# stm.net
KiCad netlist of a schematic drawn in Altium Designer
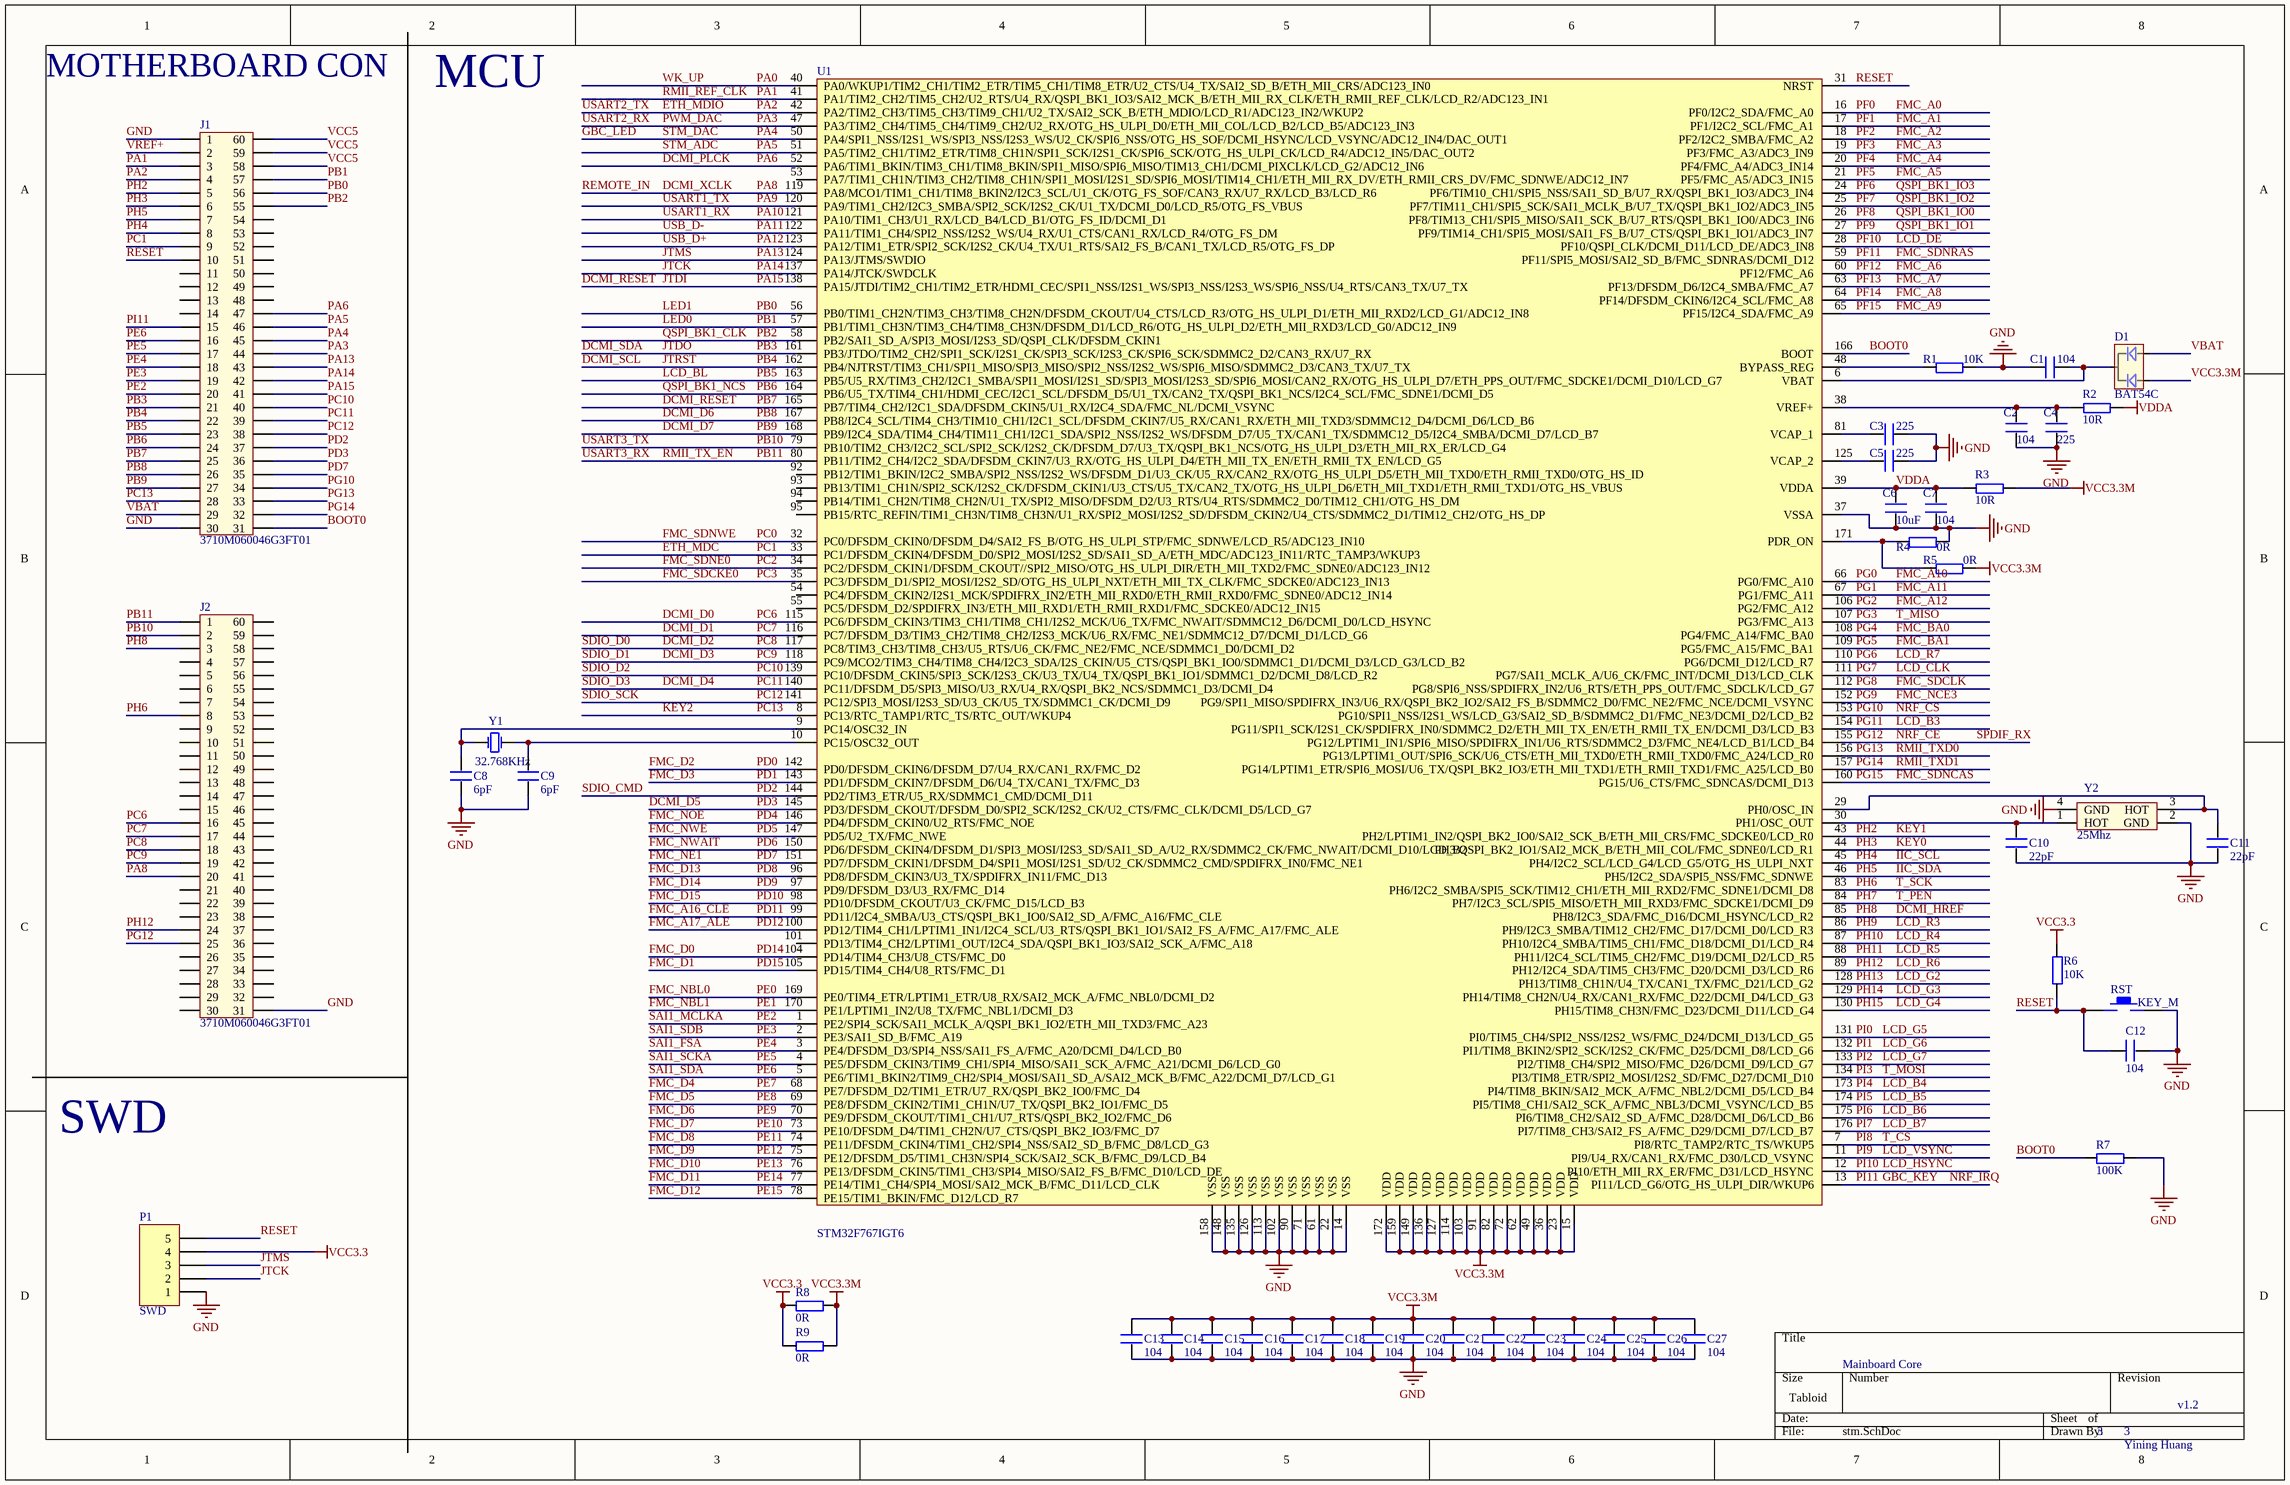
[diagram p0: stm.SchDoc]

(export (version "E")
  (design (tool "Eeschema 10.0.6"))
  (components
    (comp (ref "C1") (value "104") (footprint "0805") (libsource (lib "STM32F767核心板封装库") (part "C")))
    (comp (ref "C2") (value "104") (footprint "0805") (libsource (lib "STM32F767核心板封装库") (part "C")))
    (comp (ref "C3") (value "225") (footprint "0805") (libsource (lib "STM32F767核心板封装库") (part "C")))
    (comp (ref "C4") (value "225") (footprint "0805") (libsource (lib "STM32F767核心板封装库") (part "C")))
    (comp (ref "C5") (value "225") (footprint "0805") (libsource (lib "STM32F767核心板封装库") (part "C")))
    (comp (ref "C6") (value "10uF") (footprint "0805") (libsource (lib "STM32F767核心板封装库") (part "C")))
    (comp (ref "C7") (value "104") (footprint "0805") (libsource (lib "STM32F767核心板封装库") (part "C")))
    (comp (ref "C8") (value "6pF") (footprint "0805") (libsource (lib "STM32F767核心板封装库") (part "C")))
    (comp (ref "C9") (value "6pF") (footprint "0805") (libsource (lib "STM32F767核心板封装库") (part "C")))
    (comp (ref "C10") (value "22pF") (footprint "0805") (libsource (lib "STM32F767核心板封装库") (part "C")))
    (comp (ref "C11") (value "22pF") (footprint "0805") (libsource (lib "STM32F767核心板封装库") (part "C")))
    (comp (ref "C12") (value "104") (footprint "0805") (libsource (lib "STM32F767核心板封装库") (part "C")))
    (comp (ref "C13") (value "104") (footprint "0805") (libsource (lib "STM32F767核心板封装库") (part "C")))
    (comp (ref "C14") (value "104") (footprint "0805") (libsource (lib "STM32F767核心板封装库") (part "C")))
    (comp (ref "C15") (value "104") (footprint "0805") (libsource (lib "STM32F767核心板封装库") (part "C")))
    (comp (ref "C16") (value "104") (footprint "0805") (libsource (lib "STM32F767核心板封装库") (part "C")))
    (comp (ref "C17") (value "104") (footprint "0805") (libsource (lib "STM32F767核心板封装库") (part "C")))
    (comp (ref "C18") (value "104") (footprint "0805") (libsource (lib "STM32F767核心板封装库") (part "C")))
    (comp (ref "C19") (value "104") (footprint "0805") (libsource (lib "STM32F767核心板封装库") (part "C")))
    (comp (ref "C20") (value "104") (footprint "0805") (libsource (lib "STM32F767核心板封装库") (part "C")))
    (comp (ref "C21") (value "104") (footprint "0805") (libsource (lib "STM32F767核心板封装库") (part "C")))
    (comp (ref "C22") (value "104") (footprint "0805") (libsource (lib "STM32F767核心板封装库") (part "C")))
    (comp (ref "C23") (value "104") (footprint "0805") (libsource (lib "STM32F767核心板封装库") (part "C")))
    (comp (ref "C24") (value "104") (footprint "0805") (libsource (lib "STM32F767核心板封装库") (part "C")))
    (comp (ref "C25") (value "104") (footprint "0805") (libsource (lib "STM32F767核心板封装库") (part "C")))
    (comp (ref "C26") (value "104") (footprint "0805") (libsource (lib "STM32F767核心板封装库") (part "C")))
    (comp (ref "C27") (value "104") (footprint "0805") (libsource (lib "STM32F767核心板封装库") (part "C")))
    (comp (ref "D1")
      (value "BAT54C")
      (footprint "SOT-23")
      (description "双肖特基二极管")
      (libsource (lib "STM32F767核心板封装库") (part "BAT54C"))
    )
    (comp (ref "J1")
      (value "3710M060046G3FT01")
      (footprint "3710F060046G3FT01")
      (description "3710F060046G3FT01")
      (libsource (lib "STM32F767核心板封装库") (part "3710F"))
    )
    (comp (ref "J2")
      (value "3710M060046G3FT01")
      (footprint "3710F060046G3FT01")
      (description "3710F060046G3FT01")
      (libsource (lib "STM32F767核心板封装库") (part "3710F"))
    )
    (comp (ref "P1")
      (value "SWD")
      (footprint "HDR1X5")
      (description "Header, 5-Pin")
      (fields (field (name "PUBLISHER") "Altium Limited"))
      (libsource (lib "STM32F767核心板封装库") (part "Header 5"))
    )
    (comp (ref "R1") (value "10K") (footprint "0805") (libsource (lib "STM32F767核心板封装库") (part "R")))
    (comp (ref "R2") (value "10R") (footprint "0805") (libsource (lib "STM32F767核心板封装库") (part "R")))
    (comp (ref "R3") (value "10R") (footprint "0805") (libsource (lib "STM32F767核心板封装库") (part "R")))
    (comp (ref "R4") (value "0R") (footprint "0805") (libsource (lib "STM32F767核心板封装库") (part "R")))
    (comp (ref "R5") (value "0R") (footprint "0805") (libsource (lib "STM32F767核心板封装库") (part "R")))
    (comp (ref "R6") (value "10K") (footprint "0805") (libsource (lib "STM32F767核心板封装库") (part "R")))
    (comp (ref "R7") (value "100K") (footprint "0805") (libsource (lib "STM32F767核心板封装库") (part "R")))
    (comp (ref "R8") (value "0R") (footprint "0805") (libsource (lib "STM32F767核心板封装库") (part "R")))
    (comp (ref "R9") (value "0R") (footprint "0805") (libsource (lib "STM32F767核心板封装库") (part "R")))
    (comp (ref "RST")
      (value "KEY_M")
      (footprint "KEY_SOP3625")
      (libsource (lib "STM32F767核心板封装库") (part "KEY_M"))
    )
    (comp (ref "U1")
      (value "STM32F767IGT6")
      (footprint "LQFP176")
      (libsource (lib "STM32F767核心板封装库") (part "STM32F767IGT6"))
    )
    (comp (ref "Y1")
      (value "32.768KHz")
      (footprint "XTAL3215")
      (description "普通晶振")
      (fields (field (name "PUBLISHER") "Altium Limited"))
      (libsource (lib "STM32F767核心板封装库") (part "XTAL"))
    )
    (comp (ref "Y2")
      (value "25Mhz")
      (footprint "XTAL3225")
      (description "3225贴片无源晶振")
      (libsource (lib "STM32F767核心板封装库") (part "XTAL_3225"))
    )
  )
  (nets
    (net (code "1") (name "/BOOT0") (class "Default")
      (node (ref "J1") (pin "31") (pinfunction "31_31") (pintype "passive"))
      (node (ref "R7") (pin "1") (pintype "passive"))
      (node (ref "U1") (pin "166") (pinfunction "BOOT_166") (pintype "passive"))
    )
    (net (code "2") (name "/DCMI_D0") (class "Default")
      (node (ref "J2") (pin "16") (pinfunction "16_16") (pintype "passive"))
      (node (ref "U1") (pin "115") (pinfunction "PC6/DFSDM_CKIN3/TIM3_CH1/TIM8_CH1/I2S2_MCK/U6_TX/FMC_NWAIT/SDMMC12_D6/DCMI_D0/LCD_HSYNC_115") (pintype "passive"))
    )
    (net (code "3") (name "/DCMI_D1") (class "Default")
      (node (ref "J2") (pin "17") (pinfunction "17_17") (pintype "passive"))
      (node (ref "U1") (pin "116") (pinfunction "PC7/DFSDM_D3/TIM3_CH2/TIM8_CH2/I2S3_MCK/U6_RX/FMC_NE1/SDMMC12_D7/DCMI_D1/LCD_G6_116") (pintype "passive"))
    )
    (net (code "4") (name "/DCMI_D2") (class "Default")
      (node (ref "J2") (pin "18") (pinfunction "18_18") (pintype "passive"))
      (node (ref "U1") (pin "117") (pinfunction "PC8/TIM3_CH3/TIM8_CH3/U5_RTS/U6_CK/FMC_NE2/FMC_NCE/SDMMC1_D0/DCMI_D2_117") (pintype "passive"))
    )
    (net (code "5") (name "/DCMI_D3") (class "Default")
      (node (ref "J2") (pin "19") (pinfunction "19_19") (pintype "passive"))
      (node (ref "U1") (pin "118") (pinfunction "PC9/MCO2/TIM3_CH4/TIM8_CH4/I2C3_SDA/I2S_CKIN/U5_CTS/QSPI_BK1_IO0/SDMMC1_D1/DCMI_D3/LCD_G3/LCD_B2_118") (pintype "passive"))
    )
    (net (code "6") (name "/DCMI_D4") (class "Default")
      (node (ref "J1") (pin "39") (pinfunction "39_39") (pintype "passive"))
      (node (ref "U1") (pin "140") (pinfunction "PC11/DFSDM_D5/SPI3_MISO/U3_RX/U4_RX/QSPI_BK2_NCS/SDMMC1_D3/DCMI_D4_140") (pintype "passive"))
    )
    (net (code "7") (name "/DCMI_D5") (class "Default")
      (node (ref "J1") (pin "36") (pinfunction "36_36") (pintype "passive"))
      (node (ref "U1") (pin "145") (pinfunction "PD3/DFSDM_CKOUT/DFSDM_D0/SPI2_SCK/I2S2_CK/U2_CTS/FMC_CLK/DCMI_D5/LCD_G7_145") (pintype "passive"))
    )
    (net (code "8") (name "/DCMI_D6") (class "Default")
      (node (ref "J1") (pin "26") (pinfunction "26_26") (pintype "passive"))
      (node (ref "U1") (pin "167") (pinfunction "PB8/I2C4_SCL/TIM4_CH3/TIM10_CH1/I2C1_SCL/DFSDM_CKIN7/U5_RX/CAN1_RX/ETH_MII_TXD3/SDMMC12_D4/DCMI_D6/LCD_B6_167") (pintype "passive"))
    )
    (net (code "9") (name "/DCMI_D7") (class "Default")
      (node (ref "J1") (pin "27") (pinfunction "27_27") (pintype "passive"))
      (node (ref "U1") (pin "168") (pinfunction "PB9/I2C4_SDA/TIM4_CH4/TIM11_CH1/I2C1_SDA/SPI2_NSS/I2S2_WS/DFSDM_D7/U5_TX/CAN1_TX/SDMMC12_D5/I2C4_SMBA/DCMI_D7/LCD_B7_168") (pintype "passive"))
    )
    (net (code "10") (name "/DCMI_HREF") (class "Default")
      (node (ref "J2") (pin "3") (pinfunction "3_3") (pintype "passive"))
      (node (ref "U1") (pin "85") (pinfunction "PH8/I2C3_SDA/FMC_D16/DCMI_HSYNC/LCD_R2_85") (pintype "passive"))
    )
    (net (code "11") (name "/DCMI_PLCK") (class "Default")
      (node (ref "J1") (pin "47") (pinfunction "47_47") (pintype "passive"))
      (node (ref "U1") (pin "52") (pinfunction "PA6/TIM1_BKIN/TIM3_CH1/TIM8_BKIN/SPI1_MISO/SPI6_MISO/TIM13_CH1/DCMI_PIXCLK/LCD_G2/ADC12_IN6_52") (pintype "passive"))
    )
    (net (code "12") (name "/DCMI_RESET") (class "Default")
      (node (ref "J1") (pin "25") (pinfunction "25_25") (pintype "passive"))
      (node (ref "J1") (pin "41") (pinfunction "41_41") (pintype "passive"))
      (node (ref "U1") (pin "138") (pinfunction "PA15/JTDI/TIM2_CH1/TIM2_ETR/HDMI_CEC/SPI1_NSS/I2S1_WS/SPI3_NSS/I2S3_WS/SPI6_NSS/U4_RTS/CAN3_TX/U7_TX_138") (pintype "passive"))
      (node (ref "U1") (pin "165") (pinfunction "PB7/TIM4_CH2/I2C1_SDA/DFSDM_CKIN5/U1_RX/I2C4_SDA/FMC_NL/DCMI_VSYNC_165") (pintype "passive"))
    )
    (net (code "13") (name "/DCMI_SCL") (class "Default")
      (node (ref "J1") (pin "22") (pinfunction "22_22") (pintype "passive"))
      (node (ref "U1") (pin "162") (pinfunction "PB4/NJTRST/TIM3_CH1/SPI1_MISO/SPI3_MISO/SPI2_NSS/I2S2_WS/SPI6_MISO/SDMMC2_D3/CAN3_TX/U7_TX_162") (pintype "passive"))
    )
    (net (code "14") (name "/DCMI_SDA") (class "Default")
      (node (ref "J1") (pin "21") (pinfunction "21_21") (pintype "passive"))
      (node (ref "U1") (pin "161") (pinfunction "PB3/JTDO/TIM2_CH2/SPI1_SCK/I2S1_CK/SPI3_SCK/I2S3_CK/SPI6_SCK/SDMMC2_D2/CAN3_RX/U7_RX_161") (pintype "passive"))
    )
    (net (code "15") (name "/DCMI_XCLK") (class "Default")
      (node (ref "J2") (pin "20") (pinfunction "20_20") (pintype "passive"))
      (node (ref "U1") (pin "119") (pinfunction "PA8/MCO1/TIM1_CH1/TIM8_BKIN2/I2C3_SCL/U1_CK/OTG_FS_SOF/CAN3_RX/U7_RX/LCD_B3/LCD_R6_119") (pintype "passive"))
    )
    (net (code "16") (name "/ETH_MDC") (class "Default")
      (node (ref "J1") (pin "9") (pinfunction "9_9") (pintype "passive"))
      (node (ref "U1") (pin "33") (pinfunction "PC1/DFSDM_CKIN4/DFSDM_D0/SPI2_MOSI/I2S2_SD/SAI1_SD_A/ETH_MDC/ADC123_IN11/RTC_TAMP3/WKUP3_33") (pintype "passive"))
    )
    (net (code "17") (name "/ETH_MDIO") (class "Default")
      (node (ref "J1") (pin "4") (pinfunction "4_4") (pintype "passive"))
      (node (ref "U1") (pin "42") (pinfunction "PA2/TIM2_CH3/TIM5_CH3/TIM9_CH1/U2_TX/SAI2_SCK_B/ETH_MDIO/LCD_R1/ADC123_IN2/WKUP2_42") (pintype "passive"))
    )
    (net (code "18") (name "/FMC_A0") (class "Default")
      (node (ref "U1") (pin "16") (pinfunction "PF0/I2C2_SDA/FMC_A0_16") (pintype "passive"))
    )
    (net (code "19") (name "/FMC_A1") (class "Default")
      (node (ref "U1") (pin "17") (pinfunction "PF1/I2C2_SCL/FMC_A1_17") (pintype "passive"))
    )
    (net (code "20") (name "/FMC_A2") (class "Default")
      (node (ref "U1") (pin "18") (pinfunction "PF2/I2C2_SMBA/FMC_A2_18") (pintype "passive"))
    )
    (net (code "21") (name "/FMC_A3") (class "Default")
      (node (ref "U1") (pin "19") (pinfunction "PF3/FMC_A3/ADC3_IN9_19") (pintype "passive"))
    )
    (net (code "22") (name "/FMC_A4") (class "Default")
      (node (ref "U1") (pin "20") (pinfunction "PF4/FMC_A4/ADC3_IN14_20") (pintype "passive"))
    )
    (net (code "23") (name "/FMC_A5") (class "Default")
      (node (ref "U1") (pin "21") (pinfunction "PF5/FMC_A5/ADC3_IN15_21") (pintype "passive"))
    )
    (net (code "24") (name "/FMC_A6") (class "Default")
      (node (ref "U1") (pin "60") (pinfunction "PF12/FMC_A6_60") (pintype "passive"))
    )
    (net (code "25") (name "/FMC_A7") (class "Default")
      (node (ref "U1") (pin "63") (pinfunction "PF13/DFSDM_D6/I2C4_SMBA/FMC_A7_63") (pintype "passive"))
    )
    (net (code "26") (name "/FMC_A8") (class "Default")
      (node (ref "U1") (pin "64") (pinfunction "PF14/DFSDM_CKIN6/I2C4_SCL/FMC_A8_64") (pintype "passive"))
    )
    (net (code "27") (name "/FMC_A9") (class "Default")
      (node (ref "U1") (pin "65") (pinfunction "PF15/I2C4_SDA/FMC_A9_65") (pintype "passive"))
    )
    (net (code "28") (name "/FMC_A10") (class "Default")
      (node (ref "U1") (pin "66") (pinfunction "PG0/FMC_A10_66") (pintype "passive"))
    )
    (net (code "29") (name "/FMC_A11") (class "Default")
      (node (ref "U1") (pin "67") (pinfunction "PG1/FMC_A11_67") (pintype "passive"))
    )
    (net (code "30") (name "/FMC_A12") (class "Default")
      (node (ref "U1") (pin "106") (pinfunction "PG2/FMC_A12_106") (pintype "passive"))
    )
    (net (code "31") (name "/FMC_A16_CLE") (class "Default")
      (node (ref "U1") (pin "99") (pinfunction "PD11/I2C4_SMBA/U3_CTS/QSPI_BK1_IO0/SAI2_SD_A/FMC_A16/FMC_CLE_99") (pintype "passive"))
    )
    (net (code "32") (name "/FMC_A17_ALE") (class "Default")
      (node (ref "U1") (pin "100") (pinfunction "PD12/TIM4_CH1/LPTIM1_IN1/I2C4_SCL/U3_RTS/QSPI_BK1_IO1/SAI2_FS_A/FMC_A17/FMC_ALE_100") (pintype "passive"))
    )
    (net (code "33") (name "/FMC_BA0") (class "Default")
      (node (ref "U1") (pin "108") (pinfunction "PG4/FMC_A14/FMC_BA0_108") (pintype "passive"))
    )
    (net (code "34") (name "/FMC_BA1") (class "Default")
      (node (ref "U1") (pin "109") (pinfunction "PG5/FMC_A15/FMC_BA1_109") (pintype "passive"))
    )
    (net (code "35") (name "/FMC_D0") (class "Default")
      (node (ref "U1") (pin "104") (pinfunction "PD14/TIM4_CH3/U8_CTS/FMC_D0_104") (pintype "passive"))
    )
    (net (code "36") (name "/FMC_D1") (class "Default")
      (node (ref "U1") (pin "105") (pinfunction "PD15/TIM4_CH4/U8_RTS/FMC_D1_105") (pintype "passive"))
    )
    (net (code "37") (name "/FMC_D2") (class "Default")
      (node (ref "U1") (pin "142") (pinfunction "PD0/DFSDM_CKIN6/DFSDM_D7/U4_RX/CAN1_RX/FMC_D2_142") (pintype "passive"))
    )
    (net (code "38") (name "/FMC_D3") (class "Default")
      (node (ref "U1") (pin "143") (pinfunction "PD1/DFSDM_CKIN7/DFSDM_D6/U4_TX/CAN1_TX/FMC_D3_143") (pintype "passive"))
    )
    (net (code "39") (name "/FMC_D4") (class "Default")
      (node (ref "U1") (pin "68") (pinfunction "PE7/DFSDM_D2/TIM1_ETR/U7_RX/QSPI_BK2_IO0/FMC_D4_68") (pintype "passive"))
    )
    (net (code "40") (name "/FMC_D5") (class "Default")
      (node (ref "U1") (pin "69") (pinfunction "PE8/DFSDM_CKIN2/TIM1_CH1N/U7_TX/QSPI_BK2_IO1/FMC_D5_69") (pintype "passive"))
    )
    (net (code "41") (name "/FMC_D6") (class "Default")
      (node (ref "U1") (pin "70") (pinfunction "PE9/DFSDM_CKOUT/TIM1_CH1/U7_RTS/QSPI_BK2_IO2/FMC_D6_70") (pintype "passive"))
    )
    (net (code "42") (name "/FMC_D7") (class "Default")
      (node (ref "U1") (pin "73") (pinfunction "PE10/DFSDM_D4/TIM1_CH2N/U7_CTS/QSPI_BK2_IO3/FMC_D7_73") (pintype "passive"))
    )
    (net (code "43") (name "/FMC_D8") (class "Default")
      (node (ref "U1") (pin "74") (pinfunction "PE11/DFSDM_CKIN4/TIM1_CH2/SPI4_NSS/SAI2_SD_B/FMC_D8/LCD_G3_74") (pintype "passive"))
    )
    (net (code "44") (name "/FMC_D9") (class "Default")
      (node (ref "U1") (pin "75") (pinfunction "PE12/DFSDM_D5/TIM1_CH3N/SPI4_SCK/SAI2_SCK_B/FMC_D9/LCD_B4_75") (pintype "passive"))
    )
    (net (code "45") (name "/FMC_D10") (class "Default")
      (node (ref "U1") (pin "76") (pinfunction "PE13/DFSDM_CKIN5/TIM1_CH3/SPI4_MISO/SAI2_FS_B/FMC_D10/LCD_DE_76") (pintype "passive"))
    )
    (net (code "46") (name "/FMC_D11") (class "Default")
      (node (ref "U1") (pin "77") (pinfunction "PE14/TIM1_CH4/SPI4_MOSI/SAI2_MCK_B/FMC_D11/LCD_CLK_77") (pintype "passive"))
    )
    (net (code "47") (name "/FMC_D12") (class "Default")
      (node (ref "U1") (pin "78") (pinfunction "PE15/TIM1_BKIN/FMC_D12/LCD_R7_78") (pintype "passive"))
    )
    (net (code "48") (name "/FMC_D13") (class "Default")
      (node (ref "U1") (pin "96") (pinfunction "PD8/DFSDM_CKIN3/U3_TX/SPDIFRX_IN11/FMC_D13_96") (pintype "passive"))
    )
    (net (code "49") (name "/FMC_D14") (class "Default")
      (node (ref "U1") (pin "97") (pinfunction "PD9/DFSDM_D3/U3_RX/FMC_D14_97") (pintype "passive"))
    )
    (net (code "50") (name "/FMC_D15") (class "Default")
      (node (ref "U1") (pin "98") (pinfunction "PD10/DFSDM_CKOUT/U3_CK/FMC_D15/LCD_B3_98") (pintype "passive"))
    )
    (net (code "51") (name "/FMC_NBL0") (class "Default")
      (node (ref "U1") (pin "169") (pinfunction "PE0/TIM4_ETR/LPTIM1_ETR/U8_RX/SAI2_MCK_A/FMC_NBL0/DCMI_D2_169") (pintype "passive"))
    )
    (net (code "52") (name "/FMC_NBL1") (class "Default")
      (node (ref "U1") (pin "170") (pinfunction "PE1/LPTIM1_IN2/U8_TX/FMC_NBL1/DCMI_D3_170") (pintype "passive"))
    )
    (net (code "53") (name "/FMC_NCE3") (class "Default")
      (node (ref "U1") (pin "152") (pinfunction "PG9/SPI1_MISO/SPDIFRX_IN3/U6_RX/QSPI_BK2_IO2/SAI2_FS_B/SDMMC2_D0/FMC_NE2/FMC_NCE/DCMI_VSYNC_152") (pintype "passive"))
    )
    (net (code "54") (name "/FMC_NE1") (class "Default")
      (node (ref "J1") (pin "35") (pinfunction "35_35") (pintype "passive"))
      (node (ref "U1") (pin "151") (pinfunction "PD7/DFSDM_CKIN1/DFSDM_D4/SPI1_MOSI/I2S1_SD/U2_CK/SDMMC2_CMD/SPDIFRX_IN0/FMC_NE1_151") (pintype "passive"))
    )
    (net (code "55") (name "/FMC_NOE") (class "Default")
      (node (ref "U1") (pin "146") (pinfunction "PD4/DFSDM_CKIN0/U2_RTS/FMC_NOE_146") (pintype "passive"))
    )
    (net (code "56") (name "/FMC_NWAIT") (class "Default")
      (node (ref "U1") (pin "150") (pinfunction "PD6/DFSDM_CKIN4/DFSDM_D1/SPI3_MOSI/I2S3_SD/SAI1_SD_A/U2_RX/SDMMC2_CK/FMC_NWAIT/DCMI_D10/LCD_B2_150") (pintype "passive"))
    )
    (net (code "57") (name "/FMC_NWE") (class "Default")
      (node (ref "U1") (pin "147") (pinfunction "PD5/U2_TX/FMC_NWE_147") (pintype "passive"))
    )
    (net (code "58") (name "/FMC_SDCKE0") (class "Default")
      (node (ref "U1") (pin "35") (pinfunction "PC3/DFSDM_D1/SPI2_MOSI/I2S2_SD/OTG_HS_ULPI_NXT/ETH_MII_TX_CLK/FMC_SDCKE0/ADC123_IN13_35") (pintype "passive"))
    )
    (net (code "59") (name "/FMC_SDCLK") (class "Default")
      (node (ref "U1") (pin "112") (pinfunction "PG8/SPI6_NSS/SPDIFRX_IN2/U6_RTS/ETH_PPS_OUT/FMC_SDCLK/LCD_G7_112") (pintype "passive"))
    )
    (net (code "60") (name "/FMC_SDNCAS") (class "Default")
      (node (ref "U1") (pin "160") (pinfunction "PG15/U6_CTS/FMC_SDNCAS/DCMI_D13_160") (pintype "passive"))
    )
    (net (code "61") (name "/FMC_SDNE0") (class "Default")
      (node (ref "U1") (pin "34") (pinfunction "PC2/DFSDM_CKIN1/DFSDM_CKOUT//SPI2_MISO/OTG_HS_ULPI_DIR/ETH_MII_TXD2/FMC_SDNE0/ADC123_IN12_34") (pintype "passive"))
    )
    (net (code "62") (name "/FMC_SDNRAS") (class "Default")
      (node (ref "U1") (pin "59") (pinfunction "PF11/SPI5_MOSI/SAI2_SD_B/FMC_SDNRAS/DCMI_D12_59") (pintype "passive"))
    )
    (net (code "63") (name "/FMC_SDNWE") (class "Default")
      (node (ref "U1") (pin "32") (pinfunction "PC0/DFSDM_CKIN0/DFSDM_D4/SAI2_FS_B/OTG_HS_ULPI_STP/FMC_SDNWE/LCD_R5/ADC123_IN10_32") (pintype "passive"))
    )
    (net (code "64") (name "/GBC_KEY") (class "Default")
      (node (ref "J1") (pin "15") (pinfunction "15_15") (pintype "passive"))
      (node (ref "U1") (pin "13") (pinfunction "PI11/LCD_G6/OTG_HS_ULPI_DIR/WKUP6_13") (pintype "passive"))
    )
    (net (code "65") (name "/GBC_LED") (class "Default")
      (node (ref "J1") (pin "45") (pinfunction "45_45") (pintype "passive"))
      (node (ref "U1") (pin "50") (pinfunction "PA4/SPI1_NSS/I2S1_WS/SPI3_NSS/I2S3_WS/U2_CK/SPI6_NSS/OTG_HS_SOF/DCMI_HSYNC/LCD_VSYNC/ADC12_IN4/DAC_OUT1_50") (pintype "passive"))
    )
    (net (code "66") (name "/IIC_SCL") (class "Default")
      (node (ref "J1") (pin "8") (pinfunction "8_8") (pintype "passive"))
      (node (ref "U1") (pin "45") (pinfunction "PH4/I2C2_SCL/LCD_G4/LCD_G5/OTG_HS_ULPI_NXT_45") (pintype "passive"))
    )
    (net (code "67") (name "/IIC_SDA") (class "Default")
      (node (ref "J1") (pin "7") (pinfunction "7_7") (pintype "passive"))
      (node (ref "U1") (pin "46") (pinfunction "PH5/I2C2_SDA/SPI5_NSS/FMC_SDNWE_46") (pintype "passive"))
    )
    (net (code "68") (name "/JTCK") (class "Default")
      (node (ref "J1") (pin "42") (pinfunction "42_42") (pintype "passive"))
      (node (ref "P1") (pin "2") (pinfunction "2_2") (pintype "passive"))
      (node (ref "U1") (pin "137") (pinfunction "PA14/JTCK/SWDCLK_137") (pintype "passive"))
    )
    (net (code "69") (name "/JTMS") (class "Default")
      (node (ref "J1") (pin "43") (pinfunction "43_43") (pintype "passive"))
      (node (ref "P1") (pin "3") (pinfunction "3_3") (pintype "passive"))
      (node (ref "U1") (pin "124") (pinfunction "PA13/JTMS/SWDIO_124") (pintype "passive"))
    )
    (net (code "70") (name "/KEY0") (class "Default")
      (node (ref "J1") (pin "6") (pinfunction "6_6") (pintype "passive"))
      (node (ref "U1") (pin "44") (pinfunction "PH3/QSPI_BK2_IO1/SAI2_MCK_B/ETH_MII_COL/FMC_SDNE0/LCD_R1_44") (pintype "passive"))
    )
    (net (code "71") (name "/KEY1") (class "Default")
      (node (ref "J1") (pin "5") (pinfunction "5_5") (pintype "passive"))
      (node (ref "U1") (pin "43") (pinfunction "PH2/LPTIM1_IN2/QSPI_BK2_IO0/SAI2_SCK_B/ETH_MII_CRS/FMC_SDCKE0/LCD_R0_43") (pintype "passive"))
    )
    (net (code "72") (name "/KEY2") (class "Default")
      (node (ref "J1") (pin "28") (pinfunction "28_28") (pintype "passive"))
      (node (ref "U1") (pin "8") (pinfunction "PC13/RTC_TAMP1/RTC_TS/RTC_OUT/WKUP4_8") (pintype "passive"))
    )
    (net (code "73") (name "/LCD_B3") (class "Default")
      (node (ref "U1") (pin "154") (pinfunction "PG11/SPI1_SCK/I2S1_CK/SPDIFRX_IN0/SDMMC2_D2/ETH_MII_TX_EN/ETH_RMII_TX_EN/DCMI_D3/LCD_B3_154") (pintype "passive"))
    )
    (net (code "74") (name "/LCD_B4") (class "Default")
      (node (ref "U1") (pin "173") (pinfunction "PI4/TIM8_BKIN/SAI2_MCK_A/FMC_NBL2/DCMI_D5/LCD_B4_173") (pintype "passive"))
    )
    (net (code "75") (name "/LCD_B5") (class "Default")
      (node (ref "U1") (pin "174") (pinfunction "PI5/TIM8_CH1/SAI2_SCK_A/FMC_NBL3/DCMI_VSYNC/LCD_B5_174") (pintype "passive"))
    )
    (net (code "76") (name "/LCD_B6") (class "Default")
      (node (ref "U1") (pin "175") (pinfunction "PI6/TIM8_CH2/SAI2_SD_A/FMC_D28/DCMI_D6/LCD_B6_175") (pintype "passive"))
    )
    (net (code "77") (name "/LCD_B7") (class "Default")
      (node (ref "U1") (pin "176") (pinfunction "PI7/TIM8_CH3/SAI2_FS_A/FMC_D29/DCMI_D7/LCD_B7_176") (pintype "passive"))
    )
    (net (code "78") (name "/LCD_BL") (class "Default")
      (node (ref "J1") (pin "23") (pinfunction "23_23") (pintype "passive"))
      (node (ref "U1") (pin "163") (pinfunction "PB5/U5_RX/TIM3_CH2/I2C1_SMBA/SPI1_MOSI/I2S1_SD/SPI3_MOSI/I2S3_SD/SPI6_MOSI/CAN2_RX/OTG_HS_ULPI_D7/ETH_PPS_OUT/FMC_SDCKE1/DCMI_D10/LCD_G7_163") (pintype "passive"))
    )
    (net (code "79") (name "/LCD_CLK") (class "Default")
      (node (ref "U1") (pin "111") (pinfunction "PG7/SAI1_MCLK_A/U6_CK/FMC_INT/DCMI_D13/LCD_CLK_111") (pintype "passive"))
    )
    (net (code "80") (name "/LCD_DE") (class "Default")
      (node (ref "U1") (pin "28") (pinfunction "PF10/QSPI_CLK/DCMI_D11/LCD_DE/ADC3_IN8_28") (pintype "passive"))
    )
    (net (code "81") (name "/LCD_G2") (class "Default")
      (node (ref "U1") (pin "128") (pinfunction "PH13/TIM8_CH1N/U4_TX/CAN1_TX/FMC_D21/LCD_G2_128") (pintype "passive"))
    )
    (net (code "82") (name "/LCD_G3") (class "Default")
      (node (ref "U1") (pin "129") (pinfunction "PH14/TIM8_CH2N/U4_RX/CAN1_RX/FMC_D22/DCMI_D4/LCD_G3_129") (pintype "passive"))
    )
    (net (code "83") (name "/LCD_G4") (class "Default")
      (node (ref "U1") (pin "130") (pinfunction "PH15/TIM8_CH3N/FMC_D23/DCMI_D11/LCD_G4_130") (pintype "passive"))
    )
    (net (code "84") (name "/LCD_G5") (class "Default")
      (node (ref "U1") (pin "131") (pinfunction "PI0/TIM5_CH4/SPI2_NSS/I2S2_WS/FMC_D24/DCMI_D13/LCD_G5_131") (pintype "passive"))
    )
    (net (code "85") (name "/LCD_G6") (class "Default")
      (node (ref "U1") (pin "132") (pinfunction "PI1/TIM8_BKIN2/SPI2_SCK/I2S2_CK/FMC_D25/DCMI_D8/LCD_G6_132") (pintype "passive"))
    )
    (net (code "86") (name "/LCD_G7") (class "Default")
      (node (ref "U1") (pin "133") (pinfunction "PI2/TIM8_CH4/SPI2_MISO/FMC_D26/DCMI_D9/LCD_G7_133") (pintype "passive"))
    )
    (net (code "87") (name "/LCD_HSYNC") (class "Default")
      (node (ref "U1") (pin "12") (pinfunction "PI10/ETH_MII_RX_ER/FMC_D31/LCD_HSYNC_12") (pintype "passive"))
    )
    (net (code "88") (name "/LCD_R3") (class "Default")
      (node (ref "U1") (pin "86") (pinfunction "PH9/I2C3_SMBA/TIM12_CH2/FMC_D17/DCMI_D0/LCD_R3_86") (pintype "passive"))
    )
    (net (code "89") (name "/LCD_R4") (class "Default")
      (node (ref "U1") (pin "87") (pinfunction "PH10/I2C4_SMBA/TIM5_CH1/FMC_D18/DCMI_D1/LCD_R4_87") (pintype "passive"))
    )
    (net (code "90") (name "/LCD_R5") (class "Default")
      (node (ref "U1") (pin "88") (pinfunction "PH11/I2C4_SCL/TIM5_CH2/FMC_D19/DCMI_D2/LCD_R5_88") (pintype "passive"))
    )
    (net (code "91") (name "/LCD_R6") (class "Default")
      (node (ref "J2") (pin "24") (pinfunction "24_24") (pintype "passive"))
      (node (ref "U1") (pin "89") (pinfunction "PH12/I2C4_SDA/TIM5_CH3/FMC_D20/DCMI_D3/LCD_R6_89") (pintype "passive"))
    )
    (net (code "92") (name "/LCD_R7") (class "Default")
      (node (ref "U1") (pin "110") (pinfunction "PG6/DCMI_D12/LCD_R7_110") (pintype "passive"))
    )
    (net (code "93") (name "/LCD_VSYNC") (class "Default")
      (node (ref "U1") (pin "11") (pinfunction "PI9/U4_RX/CAN1_RX/FMC_D30/LCD_VSYNC_11") (pintype "passive"))
    )
    (net (code "94") (name "/LED0") (class "Default")
      (node (ref "J1") (pin "57") (pinfunction "57_57") (pintype "passive"))
      (node (ref "U1") (pin "57") (pinfunction "PB1/TIM1_CH3N/TIM3_CH4/TIM8_CH3N/DFSDM_D1/LCD_R6/OTG_HS_ULPI_D2/ETH_MII_RXD3/LCD_G0/ADC12_IN9_57") (pintype "passive"))
    )
    (net (code "95") (name "/LED1") (class "Default")
      (node (ref "J1") (pin "56") (pinfunction "56_56") (pintype "passive"))
      (node (ref "U1") (pin "56") (pinfunction "PB0/TIM1_CH2N/TIM3_CH3/TIM8_CH2N/DFSDM_CKOUT/U4_CTS/LCD_R3/OTG_HS_ULPI_D1/ETH_MII_RXD2/LCD_G1/ADC12_IN8_56") (pintype "passive"))
    )
    (net (code "96") (name "/NRF_CE") (class "Default")
      (node (ref "J2") (pin "25") (pinfunction "25_25") (pintype "passive"))
      (node (ref "U1") (pin "155") (pinfunction "PG12/LPTIM1_IN1/SPI6_MISO/SPDIFRX_IN1/U6_RTS/SDMMC2_D3/FMC_NE4/LCD_B1/LCD_B4_155") (pintype "passive"))
    )
    (net (code "97") (name "/NRF_CS") (class "Default")
      (node (ref "J1") (pin "34") (pinfunction "34_34") (pintype "passive"))
      (node (ref "U1") (pin "153") (pinfunction "PG10/SPI1_NSS/I2S1_WS/LCD_G3/SAI2_SD_B/SDMMC2_D1/FMC_NE3/DCMI_D2/LCD_B2_153") (pintype "passive"))
    )
    (net (code "98") (name "/PA0") (class "Default")
      (node (ref "U1") (pin "40") (pinfunction "PA0/WKUP1/TIM2_CH1/TIM2_ETR/TIM5_CH1/TIM8_ETR/U2_CTS/U4_TX/SAI2_SD_B/ETH_MII_CRS/ADC123_IN0_40") (pintype "passive"))
    )
    (net (code "99") (name "/PA1") (class "Default")
      (node (ref "J1") (pin "3") (pinfunction "3_3") (pintype "passive"))
      (node (ref "U1") (pin "41") (pinfunction "PA1/TIM2_CH2/TIM5_CH2/U2_RTS/U4_RX/QSPI_BK1_IO3/SAI2_MCK_B/ETH_MII_RX_CLK/ETH_RMII_REF_CLK/LCD_R2/ADC123_IN1_41") (pintype "passive"))
    )
    (net (code "100") (name "/PA3") (class "Default")
      (node (ref "J1") (pin "44") (pinfunction "44_44") (pintype "passive"))
      (node (ref "U1") (pin "47") (pinfunction "PA3/TIM2_CH4/TIM5_CH4/TIM9_CH2/U2_RX/OTG_HS_ULPI_D0/ETH_MII_COL/LCD_B2/LCD_B5/ADC123_IN3_47") (pintype "passive"))
    )
    (net (code "101") (name "/PA5") (class "Default")
      (node (ref "J1") (pin "46") (pinfunction "46_46") (pintype "passive"))
      (node (ref "U1") (pin "51") (pinfunction "PA5/TIM2_CH1/TIM2_ETR/TIM8_CH1N/SPI1_SCK/I2S1_CK/SPI6_SCK/OTG_HS_ULPI_CK/LCD_R4/ADC12_IN5/DAC_OUT2_51") (pintype "passive"))
    )
    (net (code "102") (name "/PA9") (class "Default")
      (node (ref "U1") (pin "120") (pinfunction "PA9/TIM1_CH2/I2C3_SMBA/SPI2_SCK/I2S2_CK/U1_TX/DCMI_D0/LCD_R5/OTG_FS_VBUS_120") (pintype "passive"))
    )
    (net (code "103") (name "/PA10") (class "Default")
      (node (ref "U1") (pin "121") (pinfunction "PA10/TIM1_CH3/U1_RX/LCD_B4/LCD_B1/OTG_FS_ID/DCMI_D1_121") (pintype "passive"))
    )
    (net (code "104") (name "/PA11") (class "Default")
      (node (ref "U1") (pin "122") (pinfunction "PA11/TIM1_CH4/SPI2_NSS/I2S2_WS/U4_RX/U1_CTS/CAN1_RX/LCD_R4/OTG_FS_DM_122") (pintype "passive"))
    )
    (net (code "105") (name "/PA12") (class "Default")
      (node (ref "U1") (pin "123") (pinfunction "PA12/TIM1_ETR/SPI2_SCK/I2S2_CK/U4_TX/U1_RTS/SAI2_FS_B/CAN1_TX/LCD_R5/OTG_FS_DP_123") (pintype "passive"))
    )
    (net (code "106") (name "/PB2") (class "Default")
      (node (ref "J1") (pin "55") (pinfunction "55_55") (pintype "passive"))
      (node (ref "U1") (pin "58") (pinfunction "PB2/SAI1_SD_A/SPI3_MOSI/I2S3_SD/QSPI_CLK/DFSDM_CKIN1_58") (pintype "passive"))
    )
    (net (code "107") (name "/PB6") (class "Default")
      (node (ref "J1") (pin "24") (pinfunction "24_24") (pintype "passive"))
      (node (ref "U1") (pin "164") (pinfunction "PB6/U5_TX/TIM4_CH1/HDMI_CEC/I2C1_SCL/DFSDM_D5/U1_TX/CAN2_TX/QSPI_BK1_NCS/I2C4_SCL/FMC_SDNE1/DCMI_D5_164") (pintype "passive"))
    )
    (net (code "108") (name "/PB10") (class "Default")
      (node (ref "J2") (pin "2") (pinfunction "2_2") (pintype "passive"))
      (node (ref "U1") (pin "79") (pinfunction "PB10/TIM2_CH3/I2C2_SCL/SPI2_SCK/I2S2_CK/DFSDM_D7/U3_TX/QSPI_BK1_NCS/OTG_HS_ULPI_D3/ETH_MII_RX_ER/LCD_G4_79") (pintype "passive"))
    )
    (net (code "109") (name "/PB11") (class "Default")
      (node (ref "J2") (pin "1") (pinfunction "1_1") (pintype "passive"))
      (node (ref "U1") (pin "80") (pinfunction "PB11/TIM2_CH4/I2C2_SDA/DFSDM_CKIN7/U3_RX/OTG_HS_ULPI_D4/ETH_MII_TX_EN/ETH_RMII_TX_EN/LCD_G5_80") (pintype "passive"))
    )
    (net (code "110") (name "/PC10") (class "Default")
      (node (ref "J1") (pin "40") (pinfunction "40_40") (pintype "passive"))
      (node (ref "U1") (pin "139") (pinfunction "PC10/DFSDM_CKIN5/SPI3_SCK/I2S3_CK/U3_TX/U4_TX/QSPI_BK1_IO1/SDMMC1_D2/DCMI_D8/LCD_R2_139") (pintype "passive"))
    )
    (net (code "111") (name "/PC12") (class "Default")
      (node (ref "J1") (pin "38") (pinfunction "38_38") (pintype "passive"))
      (node (ref "U1") (pin "141") (pinfunction "PC12/SPI3_MOSI/I2S3_SD/U3_CK/U5_TX/SDMMC1_CK/DCMI_D9_141") (pintype "passive"))
    )
    (net (code "112") (name "/PD2") (class "Default")
      (node (ref "J1") (pin "37") (pinfunction "37_37") (pintype "passive"))
      (node (ref "U1") (pin "144") (pinfunction "PD2/TIM3_ETR/U5_RX/SDMMC1_CMD/DCMI_D11_144") (pintype "passive"))
    )
    (net (code "113") (name "/PE2") (class "Default")
      (node (ref "J1") (pin "20") (pinfunction "20_20") (pintype "passive"))
      (node (ref "U1") (pin "1") (pinfunction "PE2/SPI4_SCK/SAI1_MCLK_A/QSPI_BK1_IO2/ETH_MII_TXD3/FMC_A23_1") (pintype "passive"))
    )
    (net (code "114") (name "/PE3") (class "Default")
      (node (ref "J1") (pin "19") (pinfunction "19_19") (pintype "passive"))
      (node (ref "U1") (pin "2") (pinfunction "PE3/SAI1_SD_B/FMC_A19_2") (pintype "passive"))
    )
    (net (code "115") (name "/PE4") (class "Default")
      (node (ref "J1") (pin "18") (pinfunction "18_18") (pintype "passive"))
      (node (ref "U1") (pin "3") (pinfunction "PE4/DFSDM_D3/SPI4_NSS/SAI1_FS_A/FMC_A20/DCMI_D4/LCD_B0_3") (pintype "passive"))
    )
    (net (code "116") (name "/PE5") (class "Default")
      (node (ref "J1") (pin "17") (pinfunction "17_17") (pintype "passive"))
      (node (ref "U1") (pin "4") (pinfunction "PE5/DFSDM_CKIN3/TIM9_CH1/SPI4_MISO/SAI1_SCK_A/FMC_A21/DCMI_D6/LCD_G0_4") (pintype "passive"))
    )
    (net (code "117") (name "/PE6") (class "Default")
      (node (ref "J1") (pin "16") (pinfunction "16_16") (pintype "passive"))
      (node (ref "U1") (pin "5") (pinfunction "PE6/TIM1_BKIN2/TIM9_CH2/SPI4_MOSI/SAI1_SD_A/SAI2_MCK_B/FMC_A22/DCMI_D7/LCD_G1_5") (pintype "passive"))
    )
    (net (code "118") (name "/PF6") (class "Default")
      (node (ref "U1") (pin "24") (pinfunction "PF6/TIM10_CH1/SPI5_NSS/SAI1_SD_B/U7_RX/QSPI_BK1_IO3/ADC3_IN4_24") (pintype "passive"))
    )
    (net (code "119") (name "/PF7") (class "Default")
      (node (ref "U1") (pin "25") (pinfunction "PF7/TIM11_CH1/SPI5_SCK/SAI1_MCLK_B/U7_TX/QSPI_BK1_IO2/ADC3_IN5_25") (pintype "passive"))
    )
    (net (code "120") (name "/PF8") (class "Default")
      (node (ref "U1") (pin "26") (pinfunction "PF8/TIM13_CH1/SPI5_MISO/SAI1_SCK_B/U7_RTS/QSPI_BK1_IO0/ADC3_IN6_26") (pintype "passive"))
    )
    (net (code "121") (name "/PF9") (class "Default")
      (node (ref "U1") (pin "27") (pinfunction "PF9/TIM14_CH1/SPI5_MOSI/SAI1_FS_B/U7_CTS/QSPI_BK1_IO1/ADC3_IN7_27") (pintype "passive"))
    )
    (net (code "122") (name "/PG3") (class "Default")
      (node (ref "U1") (pin "107") (pinfunction "PG3/FMC_A13_107") (pintype "passive"))
    )
    (net (code "123") (name "/PG13") (class "Default")
      (node (ref "J1") (pin "33") (pinfunction "33_33") (pintype "passive"))
      (node (ref "U1") (pin "156") (pinfunction "PG13/LPTIM1_OUT/SPI6_SCK/U6_CTS/ETH_MII_TXD0/ETH_RMII_TXD0/FMC_A24/LCD_R0_156") (pintype "passive"))
    )
    (net (code "124") (name "/PG14") (class "Default")
      (node (ref "J1") (pin "32") (pinfunction "32_32") (pintype "passive"))
      (node (ref "U1") (pin "157") (pinfunction "PG14/LPTIM1_ETR/SPI6_MOSI/U6_TX/QSPI_BK2_IO3/ETH_MII_TXD1/ETH_RMII_TXD1/FMC_A25/LCD_B0_157") (pintype "passive"))
    )
    (net (code "125") (name "/PH6") (class "Default")
      (node (ref "J2") (pin "8") (pinfunction "8_8") (pintype "passive"))
      (node (ref "U1") (pin "83") (pinfunction "PH6/I2C2_SMBA/SPI5_SCK/TIM12_CH1/ETH_MII_RXD2/FMC_SDNE1/DCMI_D8_83") (pintype "passive"))
    )
    (net (code "126") (name "/PH7") (class "Default")
      (node (ref "U1") (pin "84") (pinfunction "PH7/I2C3_SCL/SPI5_MISO/ETH_MII_RXD3/FMC_SDCKE1/DCMI_D9_84") (pintype "passive"))
    )
    (net (code "127") (name "/PI3") (class "Default")
      (node (ref "U1") (pin "134") (pinfunction "PI3/TIM8_ETR/SPI2_MOSI/I2S2_SD/FMC_D27/DCMI_D10_134") (pintype "passive"))
    )
    (net (code "128") (name "/PI8") (class "Default")
      (node (ref "U1") (pin "7") (pinfunction "PI8/RTC_TAMP2/RTC_TS/WKUP5_7") (pintype "passive"))
    )
    (net (code "129") (name "/RESET") (class "Default")
      (node (ref "C12") (pin "1") (pintype "passive"))
      (node (ref "J1") (pin "10") (pinfunction "10_10") (pintype "passive"))
      (node (ref "P1") (pin "5") (pinfunction "5_5") (pintype "passive"))
      (node (ref "R6") (pin "1") (pintype "passive"))
      (node (ref "RST") (pin "1") (pinfunction "1_1") (pintype "passive"))
      (node (ref "U1") (pin "31") (pinfunction "NRST_31") (pintype "passive"))
    )
    (net (code "130") (name "/VBAT") (class "Default")
      (node (ref "D1") (pin "2") (pintype "passive"))
      (node (ref "J1") (pin "29") (pinfunction "29_29") (pintype "passive"))
    )
    (net (code "131") (name "/VCC5") (class "Default")
      (node (ref "J1") (pin "58") (pinfunction "58_58") (pintype "passive"))
      (node (ref "J1") (pin "59") (pinfunction "59_59") (pintype "passive"))
      (node (ref "J1") (pin "60") (pinfunction "60_60") (pintype "passive"))
    )
    (net (code "132") (name "/VREF+") (class "Default")
      (node (ref "J1") (pin "2") (pinfunction "2_2") (pintype "passive"))
    )
    (net (code "133") (name "GND") (class "Default")
      (node (ref "C1") (pin "2") (pintype "passive"))
      (node (ref "C10") (pin "1") (pintype "passive"))
      (node (ref "C11") (pin "1") (pintype "passive"))
      (node (ref "C12") (pin "2") (pintype "passive"))
      (node (ref "C13") (pin "1") (pintype "passive"))
      (node (ref "C14") (pin "1") (pintype "passive"))
      (node (ref "C15") (pin "1") (pintype "passive"))
      (node (ref "C16") (pin "1") (pintype "passive"))
      (node (ref "C17") (pin "1") (pintype "passive"))
      (node (ref "C18") (pin "1") (pintype "passive"))
      (node (ref "C19") (pin "1") (pintype "passive"))
      (node (ref "C2") (pin "1") (pintype "passive"))
      (node (ref "C20") (pin "1") (pintype "passive"))
      (node (ref "C21") (pin "1") (pintype "passive"))
      (node (ref "C22") (pin "1") (pintype "passive"))
      (node (ref "C23") (pin "1") (pintype "passive"))
      (node (ref "C24") (pin "1") (pintype "passive"))
      (node (ref "C25") (pin "1") (pintype "passive"))
      (node (ref "C26") (pin "1") (pintype "passive"))
      (node (ref "C27") (pin "1") (pintype "passive"))
      (node (ref "C3") (pin "2") (pintype "passive"))
      (node (ref "C4") (pin "1") (pintype "passive"))
      (node (ref "C5") (pin "2") (pintype "passive"))
      (node (ref "C6") (pin "1") (pintype "passive"))
      (node (ref "C7") (pin "1") (pintype "passive"))
      (node (ref "C8") (pin "1") (pintype "passive"))
      (node (ref "C9") (pin "1") (pintype "passive"))
      (node (ref "J1") (pin "1") (pinfunction "1_1") (pintype "passive"))
      (node (ref "J1") (pin "30") (pinfunction "30_30") (pintype "passive"))
      (node (ref "J2") (pin "31") (pinfunction "31_31") (pintype "passive"))
      (node (ref "P1") (pin "1") (pinfunction "1_1") (pintype "passive"))
      (node (ref "R1") (pin "2") (pintype "passive"))
      (node (ref "R4") (pin "2") (pintype "passive"))
      (node (ref "R7") (pin "2") (pintype "passive"))
      (node (ref "RST") (pin "2") (pinfunction "2_2") (pintype "passive"))
      (node (ref "U1") (pin "102") (pinfunction "VSS_102") (pintype "passive"))
      (node (ref "U1") (pin "113") (pinfunction "VSS_113") (pintype "passive"))
      (node (ref "U1") (pin "126") (pinfunction "VSS_126") (pintype "passive"))
      (node (ref "U1") (pin "135") (pinfunction "VSS_135") (pintype "passive"))
      (node (ref "U1") (pin "14") (pinfunction "VSS_14") (pintype "passive"))
      (node (ref "U1") (pin "148") (pinfunction "VSS_148") (pintype "passive"))
      (node (ref "U1") (pin "158") (pinfunction "VSS_158") (pintype "passive"))
      (node (ref "U1") (pin "22") (pinfunction "VSS_22") (pintype "passive"))
      (node (ref "U1") (pin "37") (pinfunction "VSSA_37") (pintype "passive"))
      (node (ref "U1") (pin "61") (pinfunction "VSS_61") (pintype "passive"))
      (node (ref "U1") (pin "71") (pinfunction "VSS_71") (pintype "passive"))
      (node (ref "U1") (pin "90") (pinfunction "VSS_90") (pintype "passive"))
      (node (ref "Y2") (pin "2") (pinfunction "GND_2") (pintype "passive"))
      (node (ref "Y2") (pin "4") (pinfunction "GND_4") (pintype "passive"))
    )
    (net (code "134") (name "Net-(U1-BYPASS_REG)") (class "Default")
      (node (ref "R1") (pin "1") (pintype "passive"))
      (node (ref "U1") (pin "48") (pinfunction "BYPASS_REG_48") (pintype "passive"))
    )
    (net (code "135") (name "Net-(U1-PC14{slash}OSC32_IN)") (class "Default")
      (node (ref "C8") (pin "2") (pintype "passive"))
      (node (ref "U1") (pin "9") (pinfunction "PC14/OSC32_IN_9") (pintype "passive"))
      (node (ref "Y1") (pin "1") (pinfunction "OSC1_1") (pintype "passive"))
    )
    (net (code "136") (name "Net-(U1-PC15{slash}OSC32_OUT)") (class "Default")
      (node (ref "C9") (pin "2") (pintype "passive"))
      (node (ref "U1") (pin "10") (pinfunction "PC15/OSC32_OUT_10") (pintype "passive"))
      (node (ref "Y1") (pin "2") (pinfunction "OSC2_2") (pintype "passive"))
    )
    (net (code "137") (name "Net-(U1-PDR_ON)") (class "Default")
      (node (ref "R4") (pin "1") (pintype "passive"))
      (node (ref "R5") (pin "1") (pintype "passive"))
      (node (ref "U1") (pin "171") (pinfunction "PDR_ON_171") (pintype "passive"))
    )
    (net (code "138") (name "Net-(U1-PH0{slash}OSC_IN)") (class "Default")
      (node (ref "C11") (pin "2") (pintype "passive"))
      (node (ref "U1") (pin "29") (pinfunction "PH0/OSC_IN_29") (pintype "passive"))
      (node (ref "Y2") (pin "3") (pinfunction "HOT_3") (pintype "passive"))
    )
    (net (code "139") (name "Net-(U1-PH1{slash}OSC_OUT)") (class "Default")
      (node (ref "C10") (pin "2") (pintype "passive"))
      (node (ref "U1") (pin "30") (pinfunction "PH1/OSC_OUT_30") (pintype "passive"))
      (node (ref "Y2") (pin "1") (pinfunction "HOT_1") (pintype "passive"))
    )
    (net (code "140") (name "Net-(U1-VBAT)") (class "Default")
      (node (ref "C1") (pin "1") (pintype "passive"))
      (node (ref "D1") (pin "3") (pintype "passive"))
      (node (ref "U1") (pin "6") (pinfunction "VBAT_6") (pintype "passive"))
    )
    (net (code "141") (name "Net-(U1-VCAP_1)") (class "Default")
      (node (ref "C3") (pin "1") (pintype "passive"))
      (node (ref "U1") (pin "81") (pinfunction "VCAP_1_81") (pintype "passive"))
    )
    (net (code "142") (name "Net-(U1-VCAP_2)") (class "Default")
      (node (ref "C5") (pin "1") (pintype "passive"))
      (node (ref "U1") (pin "125") (pinfunction "VCAP_2_125") (pintype "passive"))
    )
    (net (code "143") (name "Net-(U1-VREF+)") (class "Default")
      (node (ref "C2") (pin "2") (pintype "passive"))
      (node (ref "C4") (pin "2") (pintype "passive"))
      (node (ref "R2") (pin "1") (pintype "passive"))
      (node (ref "U1") (pin "38") (pinfunction "VREF+_38") (pintype "passive"))
    )
    (net (code "144") (name "VCC3.3") (class "Default")
      (node (ref "P1") (pin "4") (pinfunction "4_4") (pintype "passive"))
      (node (ref "R6") (pin "2") (pintype "passive"))
      (node (ref "R8") (pin "1") (pintype "passive"))
      (node (ref "R9") (pin "1") (pintype "passive"))
    )
    (net (code "145") (name "VCC3.3M") (class "Default")
      (node (ref "C13") (pin "2") (pintype "passive"))
      (node (ref "C14") (pin "2") (pintype "passive"))
      (node (ref "C15") (pin "2") (pintype "passive"))
      (node (ref "C16") (pin "2") (pintype "passive"))
      (node (ref "C17") (pin "2") (pintype "passive"))
      (node (ref "C18") (pin "2") (pintype "passive"))
      (node (ref "C19") (pin "2") (pintype "passive"))
      (node (ref "C20") (pin "2") (pintype "passive"))
      (node (ref "C21") (pin "2") (pintype "passive"))
      (node (ref "C22") (pin "2") (pintype "passive"))
      (node (ref "C23") (pin "2") (pintype "passive"))
      (node (ref "C24") (pin "2") (pintype "passive"))
      (node (ref "C25") (pin "2") (pintype "passive"))
      (node (ref "C26") (pin "2") (pintype "passive"))
      (node (ref "C27") (pin "2") (pintype "passive"))
      (node (ref "D1") (pin "1") (pintype "passive"))
      (node (ref "R3") (pin "2") (pintype "passive"))
      (node (ref "R5") (pin "2") (pintype "passive"))
      (node (ref "R8") (pin "2") (pintype "passive"))
      (node (ref "R9") (pin "2") (pintype "passive"))
      (node (ref "U1") (pin "103") (pinfunction "VDD_103") (pintype "passive"))
      (node (ref "U1") (pin "114") (pinfunction "VDD_114") (pintype "passive"))
      (node (ref "U1") (pin "127") (pinfunction "VDD_127") (pintype "passive"))
      (node (ref "U1") (pin "136") (pinfunction "VDD_136") (pintype "passive"))
      (node (ref "U1") (pin "149") (pinfunction "VDD_149") (pintype "passive"))
      (node (ref "U1") (pin "15") (pinfunction "VDD_15") (pintype "passive"))
      (node (ref "U1") (pin "159") (pinfunction "VDD_159") (pintype "passive"))
      (node (ref "U1") (pin "172") (pinfunction "VDD_172") (pintype "passive"))
      (node (ref "U1") (pin "23") (pinfunction "VDD_23") (pintype "passive"))
      (node (ref "U1") (pin "36") (pinfunction "VDD_36") (pintype "passive"))
      (node (ref "U1") (pin "49") (pinfunction "VDD_49") (pintype "passive"))
      (node (ref "U1") (pin "62") (pinfunction "VDD_62") (pintype "passive"))
      (node (ref "U1") (pin "72") (pinfunction "VDD_72") (pintype "passive"))
      (node (ref "U1") (pin "82") (pinfunction "VDD_82") (pintype "passive"))
      (node (ref "U1") (pin "91") (pinfunction "VDD_91") (pintype "passive"))
    )
    (net (code "146") (name "VDDA") (class "Default")
      (node (ref "C6") (pin "2") (pintype "passive"))
      (node (ref "C7") (pin "2") (pintype "passive"))
      (node (ref "R2") (pin "2") (pintype "passive"))
      (node (ref "R3") (pin "1") (pintype "passive"))
      (node (ref "U1") (pin "39") (pinfunction "VDDA_39") (pintype "passive"))
    )
    (net (code "147") (name "unconnected-(J1-Pad11)") (class "Default")
      (node (ref "J1") (pin "11") (pinfunction "11_11") (pintype "passive"))
    )
    (net (code "148") (name "unconnected-(J1-Pad12)") (class "Default")
      (node (ref "J1") (pin "12") (pinfunction "12_12") (pintype "passive"))
    )
    (net (code "149") (name "unconnected-(J1-Pad13)") (class "Default")
      (node (ref "J1") (pin "13") (pinfunction "13_13") (pintype "passive"))
    )
    (net (code "150") (name "unconnected-(J1-Pad14)") (class "Default")
      (node (ref "J1") (pin "14") (pinfunction "14_14") (pintype "passive"))
    )
    (net (code "151") (name "unconnected-(J1-Pad48)") (class "Default")
      (node (ref "J1") (pin "48") (pinfunction "48_48") (pintype "passive"))
    )
    (net (code "152") (name "unconnected-(J1-Pad49)") (class "Default")
      (node (ref "J1") (pin "49") (pinfunction "49_49") (pintype "passive"))
    )
    (net (code "153") (name "unconnected-(J1-Pad50)") (class "Default")
      (node (ref "J1") (pin "50") (pinfunction "50_50") (pintype "passive"))
    )
    (net (code "154") (name "unconnected-(J1-Pad51)") (class "Default")
      (node (ref "J1") (pin "51") (pinfunction "51_51") (pintype "passive"))
    )
    (net (code "155") (name "unconnected-(J1-Pad52)") (class "Default")
      (node (ref "J1") (pin "52") (pinfunction "52_52") (pintype "passive"))
    )
    (net (code "156") (name "unconnected-(J1-Pad53)") (class "Default")
      (node (ref "J1") (pin "53") (pinfunction "53_53") (pintype "passive"))
    )
    (net (code "157") (name "unconnected-(J1-Pad54)") (class "Default")
      (node (ref "J1") (pin "54") (pinfunction "54_54") (pintype "passive"))
    )
    (net (code "158") (name "unconnected-(J2-Pad4)") (class "Default")
      (node (ref "J2") (pin "4") (pinfunction "4_4") (pintype "passive"))
    )
    (net (code "159") (name "unconnected-(J2-Pad5)") (class "Default")
      (node (ref "J2") (pin "5") (pinfunction "5_5") (pintype "passive"))
    )
    (net (code "160") (name "unconnected-(J2-Pad6)") (class "Default")
      (node (ref "J2") (pin "6") (pinfunction "6_6") (pintype "passive"))
    )
    (net (code "161") (name "unconnected-(J2-Pad7)") (class "Default")
      (node (ref "J2") (pin "7") (pinfunction "7_7") (pintype "passive"))
    )
    (net (code "162") (name "unconnected-(J2-Pad9)") (class "Default")
      (node (ref "J2") (pin "9") (pinfunction "9_9") (pintype "passive"))
    )
    (net (code "163") (name "unconnected-(J2-Pad10)") (class "Default")
      (node (ref "J2") (pin "10") (pinfunction "10_10") (pintype "passive"))
    )
    (net (code "164") (name "unconnected-(J2-Pad11)") (class "Default")
      (node (ref "J2") (pin "11") (pinfunction "11_11") (pintype "passive"))
    )
    (net (code "165") (name "unconnected-(J2-Pad12)") (class "Default")
      (node (ref "J2") (pin "12") (pinfunction "12_12") (pintype "passive"))
    )
    (net (code "166") (name "unconnected-(J2-Pad13)") (class "Default")
      (node (ref "J2") (pin "13") (pinfunction "13_13") (pintype "passive"))
    )
    (net (code "167") (name "unconnected-(J2-Pad14)") (class "Default")
      (node (ref "J2") (pin "14") (pinfunction "14_14") (pintype "passive"))
    )
    (net (code "168") (name "unconnected-(J2-Pad15)") (class "Default")
      (node (ref "J2") (pin "15") (pinfunction "15_15") (pintype "passive"))
    )
    (net (code "169") (name "unconnected-(J2-Pad21)") (class "Default")
      (node (ref "J2") (pin "21") (pinfunction "21_21") (pintype "passive"))
    )
    (net (code "170") (name "unconnected-(J2-Pad22)") (class "Default")
      (node (ref "J2") (pin "22") (pinfunction "22_22") (pintype "passive"))
    )
    (net (code "171") (name "unconnected-(J2-Pad23)") (class "Default")
      (node (ref "J2") (pin "23") (pinfunction "23_23") (pintype "passive"))
    )
    (net (code "172") (name "unconnected-(J2-Pad26)") (class "Default")
      (node (ref "J2") (pin "26") (pinfunction "26_26") (pintype "passive"))
    )
    (net (code "173") (name "unconnected-(J2-Pad27)") (class "Default")
      (node (ref "J2") (pin "27") (pinfunction "27_27") (pintype "passive"))
    )
    (net (code "174") (name "unconnected-(J2-Pad28)") (class "Default")
      (node (ref "J2") (pin "28") (pinfunction "28_28") (pintype "passive"))
    )
    (net (code "175") (name "unconnected-(J2-Pad29)") (class "Default")
      (node (ref "J2") (pin "29") (pinfunction "29_29") (pintype "passive"))
    )
    (net (code "176") (name "unconnected-(J2-Pad30)") (class "Default")
      (node (ref "J2") (pin "30") (pinfunction "30_30") (pintype "passive"))
    )
    (net (code "177") (name "unconnected-(J2-Pad32)") (class "Default")
      (node (ref "J2") (pin "32") (pinfunction "32_32") (pintype "passive"))
    )
    (net (code "178") (name "unconnected-(J2-Pad33)") (class "Default")
      (node (ref "J2") (pin "33") (pinfunction "33_33") (pintype "passive"))
    )
    (net (code "179") (name "unconnected-(J2-Pad34)") (class "Default")
      (node (ref "J2") (pin "34") (pinfunction "34_34") (pintype "passive"))
    )
    (net (code "180") (name "unconnected-(J2-Pad35)") (class "Default")
      (node (ref "J2") (pin "35") (pinfunction "35_35") (pintype "passive"))
    )
    (net (code "181") (name "unconnected-(J2-Pad36)") (class "Default")
      (node (ref "J2") (pin "36") (pinfunction "36_36") (pintype "passive"))
    )
    (net (code "182") (name "unconnected-(J2-Pad37)") (class "Default")
      (node (ref "J2") (pin "37") (pinfunction "37_37") (pintype "passive"))
    )
    (net (code "183") (name "unconnected-(J2-Pad38)") (class "Default")
      (node (ref "J2") (pin "38") (pinfunction "38_38") (pintype "passive"))
    )
    (net (code "184") (name "unconnected-(J2-Pad39)") (class "Default")
      (node (ref "J2") (pin "39") (pinfunction "39_39") (pintype "passive"))
    )
    (net (code "185") (name "unconnected-(J2-Pad40)") (class "Default")
      (node (ref "J2") (pin "40") (pinfunction "40_40") (pintype "passive"))
    )
    (net (code "186") (name "unconnected-(J2-Pad41)") (class "Default")
      (node (ref "J2") (pin "41") (pinfunction "41_41") (pintype "passive"))
    )
    (net (code "187") (name "unconnected-(J2-Pad42)") (class "Default")
      (node (ref "J2") (pin "42") (pinfunction "42_42") (pintype "passive"))
    )
    (net (code "188") (name "unconnected-(J2-Pad43)") (class "Default")
      (node (ref "J2") (pin "43") (pinfunction "43_43") (pintype "passive"))
    )
    (net (code "189") (name "unconnected-(J2-Pad44)") (class "Default")
      (node (ref "J2") (pin "44") (pinfunction "44_44") (pintype "passive"))
    )
    (net (code "190") (name "unconnected-(J2-Pad45)") (class "Default")
      (node (ref "J2") (pin "45") (pinfunction "45_45") (pintype "passive"))
    )
    (net (code "191") (name "unconnected-(J2-Pad46)") (class "Default")
      (node (ref "J2") (pin "46") (pinfunction "46_46") (pintype "passive"))
    )
    (net (code "192") (name "unconnected-(J2-Pad47)") (class "Default")
      (node (ref "J2") (pin "47") (pinfunction "47_47") (pintype "passive"))
    )
    (net (code "193") (name "unconnected-(J2-Pad48)") (class "Default")
      (node (ref "J2") (pin "48") (pinfunction "48_48") (pintype "passive"))
    )
    (net (code "194") (name "unconnected-(J2-Pad49)") (class "Default")
      (node (ref "J2") (pin "49") (pinfunction "49_49") (pintype "passive"))
    )
    (net (code "195") (name "unconnected-(J2-Pad50)") (class "Default")
      (node (ref "J2") (pin "50") (pinfunction "50_50") (pintype "passive"))
    )
    (net (code "196") (name "unconnected-(J2-Pad51)") (class "Default")
      (node (ref "J2") (pin "51") (pinfunction "51_51") (pintype "passive"))
    )
    (net (code "197") (name "unconnected-(J2-Pad52)") (class "Default")
      (node (ref "J2") (pin "52") (pinfunction "52_52") (pintype "passive"))
    )
    (net (code "198") (name "unconnected-(J2-Pad53)") (class "Default")
      (node (ref "J2") (pin "53") (pinfunction "53_53") (pintype "passive"))
    )
    (net (code "199") (name "unconnected-(J2-Pad54)") (class "Default")
      (node (ref "J2") (pin "54") (pinfunction "54_54") (pintype "passive"))
    )
    (net (code "200") (name "unconnected-(J2-Pad55)") (class "Default")
      (node (ref "J2") (pin "55") (pinfunction "55_55") (pintype "passive"))
    )
    (net (code "201") (name "unconnected-(J2-Pad56)") (class "Default")
      (node (ref "J2") (pin "56") (pinfunction "56_56") (pintype "passive"))
    )
    (net (code "202") (name "unconnected-(J2-Pad57)") (class "Default")
      (node (ref "J2") (pin "57") (pinfunction "57_57") (pintype "passive"))
    )
    (net (code "203") (name "unconnected-(J2-Pad58)") (class "Default")
      (node (ref "J2") (pin "58") (pinfunction "58_58") (pintype "passive"))
    )
    (net (code "204") (name "unconnected-(J2-Pad59)") (class "Default")
      (node (ref "J2") (pin "59") (pinfunction "59_59") (pintype "passive"))
    )
    (net (code "205") (name "unconnected-(J2-Pad60)") (class "Default")
      (node (ref "J2") (pin "60") (pinfunction "60_60") (pintype "passive"))
    )
    (net (code "206") (name "unconnected-(U1-PA7{slash}TIM1_CH1N{slash}TIM3_CH2{slash}TIM8_CH1N{slash}SPI1_MOSI{slash}I2S1_SD{slash}SPI6_MOSI{slash}TIM14_CH1{slash}ETH_MII_RX_DV{slash}ETH_RMII_CRS_DV{slash}FMC_SDNWE{slash}ADC12_IN7-Pad53)") (class "Default")
      (node (ref "U1") (pin "53") (pinfunction "PA7/TIM1_CH1N/TIM3_CH2/TIM8_CH1N/SPI1_MOSI/I2S1_SD/SPI6_MOSI/TIM14_CH1/ETH_MII_RX_DV/ETH_RMII_CRS_DV/FMC_SDNWE/ADC12_IN7_53") (pintype "passive"))
    )
    (net (code "207") (name "unconnected-(U1-PB12{slash}TIM1_BKIN{slash}I2C2_SMBA{slash}SPI2_NSS{slash}I2S2_WS{slash}DFSDM_D1{slash}U3_CK{slash}U5_RX{slash}CAN2_RX{slash}OTG_HS_ULPI_D5{slash}ETH_MII_TXD0{slash}ETH_RMII_TXD0{slash}OTG_HS_ID-Pad92)") (class "Default")
      (node (ref "U1") (pin "92") (pinfunction "PB12/TIM1_BKIN/I2C2_SMBA/SPI2_NSS/I2S2_WS/DFSDM_D1/U3_CK/U5_RX/CAN2_RX/OTG_HS_ULPI_D5/ETH_MII_TXD0/ETH_RMII_TXD0/OTG_HS_ID_92") (pintype "passive"))
    )
    (net (code "208") (name "unconnected-(U1-PB13{slash}TIM1_CH1N{slash}SPI2_SCK{slash}I2S2_CK{slash}DFSDM_CKIN1{slash}U3_CTS{slash}U5_TX{slash}CAN2_TX{slash}OTG_HS_ULPI_D6{slash}ETH_MII_TXD1{slash}ETH_RMII_TXD1{slash}OTG_HS_VBUS-Pad93)") (class "Default")
      (node (ref "U1") (pin "93") (pinfunction "PB13/TIM1_CH1N/SPI2_SCK/I2S2_CK/DFSDM_CKIN1/U3_CTS/U5_TX/CAN2_TX/OTG_HS_ULPI_D6/ETH_MII_TXD1/ETH_RMII_TXD1/OTG_HS_VBUS_93") (pintype "passive"))
    )
    (net (code "209") (name "unconnected-(U1-PB14{slash}TIM1_CH2N{slash}TIM8_CH2N{slash}U1_TX{slash}SPI2_MISO{slash}DFSDM_D2{slash}U3_RTS{slash}U4_RTS{slash}SDMMC2_D0{slash}TIM12_CH1{slash}OTG_HS_DM-Pad94)") (class "Default")
      (node (ref "U1") (pin "94") (pinfunction "PB14/TIM1_CH2N/TIM8_CH2N/U1_TX/SPI2_MISO/DFSDM_D2/U3_RTS/U4_RTS/SDMMC2_D0/TIM12_CH1/OTG_HS_DM_94") (pintype "passive"))
    )
    (net (code "210") (name "unconnected-(U1-PB15{slash}RTC_REFIN{slash}TIM1_CH3N{slash}TIM8_CH3N{slash}U1_RX{slash}SPI2_MOSI{slash}I2S2_SD{slash}DFSDM_CKIN2{slash}U4_CTS{slash}SDMMC2_D1{slash}TIM12_CH2{slash}OTG_HS_DP-Pad95)") (class "Default")
      (node (ref "U1") (pin "95") (pinfunction "PB15/RTC_REFIN/TIM1_CH3N/TIM8_CH3N/U1_RX/SPI2_MOSI/I2S2_SD/DFSDM_CKIN2/U4_CTS/SDMMC2_D1/TIM12_CH2/OTG_HS_DP_95") (pintype "passive"))
    )
    (net (code "211") (name "unconnected-(U1-PC4{slash}DFSDM_CKIN2{slash}I2S1_MCK{slash}SPDIFRX_IN2{slash}ETH_MII_RXD0{slash}ETH_RMII_RXD0{slash}FMC_SDNE0{slash}ADC12_IN14-Pad54)") (class "Default")
      (node (ref "U1") (pin "54") (pinfunction "PC4/DFSDM_CKIN2/I2S1_MCK/SPDIFRX_IN2/ETH_MII_RXD0/ETH_RMII_RXD0/FMC_SDNE0/ADC12_IN14_54") (pintype "passive"))
    )
    (net (code "212") (name "unconnected-(U1-PC5{slash}DFSDM_D2{slash}SPDIFRX_IN3{slash}ETH_MII_RXD1{slash}ETH_RMII_RXD1{slash}FMC_SDCKE0{slash}ADC12_IN15-Pad55)") (class "Default")
      (node (ref "U1") (pin "55") (pinfunction "PC5/DFSDM_D2/SPDIFRX_IN3/ETH_MII_RXD1/ETH_RMII_RXD1/FMC_SDCKE0/ADC12_IN15_55") (pintype "passive"))
    )
    (net (code "213") (name "unconnected-(U1-PD13{slash}TIM4_CH2{slash}LPTIM1_OUT{slash}I2C4_SDA{slash}QSPI_BK1_IO3{slash}SAI2_SCK_A{slash}FMC_A18-Pad101)") (class "Default")
      (node (ref "U1") (pin "101") (pinfunction "PD13/TIM4_CH2/LPTIM1_OUT/I2C4_SDA/QSPI_BK1_IO3/SAI2_SCK_A/FMC_A18_101") (pintype "passive"))
    )
  )
)
